# Top.net
KiCad netlist of a schematic drawn in Altium Designer
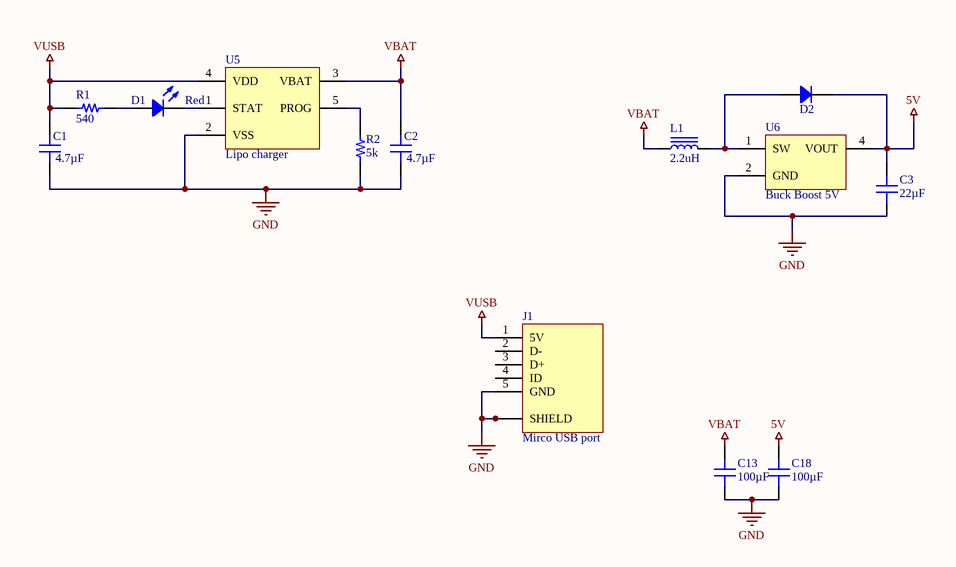
[diagram p0: Top.SchDoc]

(export (version "E")
  (design (tool "Eeschema 10.0.6"))
  (components
    (comp (ref "C1")
      (value "4.7µF")
      (footprint "CAP 0603_1608")
      (description "CAP CER 0.1UF 100V 0603 EPOXY")
      (fields
        (field (name "PART NUMBER") "GCG188R92A104KA03D")
        (field (name "MANUFACTURER") "Murata Electronics")
      )
      (libsource (lib "Celestial Altium Library - altium_library") (part "Capacitor"))
    )
    (comp (ref "C2")
      (value "4.7µF")
      (footprint "CAP 0603_1608")
      (description "CAP CER 0.1UF 100V 0603 EPOXY")
      (fields
        (field (name "PART NUMBER") "GCG188R92A104KA03D")
        (field (name "MANUFACTURER") "Murata Electronics")
      )
      (libsource (lib "Celestial Altium Library - altium_library") (part "Capacitor"))
    )
    (comp (ref "C3")
      (value "22µF")
      (footprint "CAP 1210_3225 - 2.8MM")
      (description "CAP CER 100UF 16V X5R 1210")
      (fields (field (name "PART NUMBER") "EMK325ABJ107MM-P") (field (name "MANUFACTURER") "Taiyo Yuden"))
      (libsource (lib "Celestial Altium Library - altium_library") (part "Capacitor"))
    )
    (comp (ref "C13")
      (value "100µF")
      (footprint "CAP 1210_3225 - 2.8MM")
      (description "CAP CER 100UF 16V X5R 1210")
      (fields (field (name "PART NUMBER") "EMK325ABJ107MM-P") (field (name "MANUFACTURER") "Taiyo Yuden"))
      (libsource (lib "Celestial Altium Library - altium_library") (part "Capacitor"))
    )
    (comp (ref "C18")
      (value "100µF")
      (footprint "CAP 1210_3225 - 2.8MM")
      (description "CAP CER 100UF 16V X5R 1210")
      (fields (field (name "PART NUMBER") "EMK325ABJ107MM-P") (field (name "MANUFACTURER") "Taiyo Yuden"))
      (libsource (lib "Celestial Altium Library - altium_library") (part "Capacitor"))
    )
    (comp (ref "D1")
      (value "Red")
      (footprint "LED 0603_1608 RED")
      (description "LED RED 0603 SMD")
      (fields (field (name "PART NUMBER") "5973005507F") (field (name "MANUFACTURER") "Dialight"))
      (libsource (lib "Celestial Altium Library - altium_library") (part "LED"))
    )
    (comp (ref "D2")
      (value "V1F6-M3/H")
      (footprint "SMF DO-219AB")
      (description "1A 60V SMF TRENCH SKY RECT")
      (fields (field (name "MANUFACTURER") "Vishay Semiconductor Diodes Division"))
      (libsource (lib "Celestial Altium Library - altium_library") (part "Diode"))
    )
    (comp (ref "J1")
      (value "Mirco USB port")
      (footprint "GCT_USB3131-30-0230-A_REVB")
      (description "USB - micro B USB 2.0 Receptacle Connector 5 Position Through Hole")
      (fields (field (name "MF") "Amphenol ICC") (field (name "MP") "10118194-0001LF"))
      (libsource (lib "IC") (part "USB3131-30-0230-A"))
    )
    (comp (ref "L1")
      (value "2.2uH")
      (footprint "TAIYO YUDEN MAMK2520T1R0M")
      (description "FIXED IND 470NH 3.2A 46 MOHM SMD")
      (fields (field (name "PART NUMBER") "MAKK2520TR47M") (field (name "MANUFACTURER") "Taiyo Yuden"))
      (libsource (lib "Celestial Altium Library - altium_library") (part "Inductor"))
    )
    (comp (ref "R1")
      (value "540")
      (footprint "RES 0603_1608")
      (description "RES 10K OHM 0.1% 1/16W 0603")
      (fields
        (field (name "PART NUMBER") "RNCS0603BKE10K0")
        (field (name "MANUFACTURER") "Stackpole Electronics Inc")
      )
      (libsource (lib "Celestial Altium Library - altium_library") (part "Resistor"))
    )
    (comp (ref "R2")
      (value "5k")
      (footprint "RES 0603_1608")
      (description "RES 10K OHM 0.1% 1/16W 0603")
      (fields
        (field (name "PART NUMBER") "RNCS0603BKE10K0")
        (field (name "MANUFACTURER") "Stackpole Electronics Inc")
      )
      (libsource (lib "Celestial Altium Library - altium_library") (part "Resistor"))
    )
    (comp (ref "U5")
      (value "Lipo charger")
      (footprint "TI SOT-23-5 DBV")
      (libsource (lib "IC") (part "MCP73831"))
    )
    (comp (ref "U6")
      (value "Buck Boost 5V")
      (footprint "TI SOT-23-5 DBV")
      (description "ADJ step down Buck")
      (libsource (lib "IC") (part "TPS613222A"))
    )
  )
  (nets
    (net (code "1") (name "5V") (class "Default")
      (node (ref "C18") (pin "2") (pinfunction "2_2") (pintype "passive"))
      (node (ref "C3") (pin "2") (pinfunction "2_2") (pintype "passive"))
      (node (ref "D2") (pin "2") (pinfunction "2_2") (pintype "passive"))
      (node (ref "U6") (pin "4") (pinfunction "VOUT_4") (pintype "passive"))
    )
    (net (code "2") (name "GND") (class "Default")
      (node (ref "C1") (pin "2") (pinfunction "2_2") (pintype "passive"))
      (node (ref "C13") (pin "1") (pinfunction "1_1") (pintype "passive"))
      (node (ref "C18") (pin "1") (pinfunction "1_1") (pintype "passive"))
      (node (ref "C2") (pin "2") (pinfunction "2_2") (pintype "passive"))
      (node (ref "C3") (pin "1") (pinfunction "1_1") (pintype "passive"))
      (node (ref "J1") (pin "5") (pinfunction "GND_5") (pintype "passive"))
      (node (ref "J1") (pin "S1") (pinfunction "SHIELD_S1") (pintype "passive"))
      (node (ref "J1") (pin "S2") (pinfunction "SHIELD_S2") (pintype "passive"))
      (node (ref "R2") (pin "2") (pinfunction "2_2") (pintype "passive"))
      (node (ref "U5") (pin "2") (pinfunction "VSS_2") (pintype "passive"))
      (node (ref "U6") (pin "2") (pinfunction "GND_2") (pintype "passive"))
    )
    (net (code "3") (name "Net-(D1-Pad1)") (class "Default")
      (node (ref "D1") (pin "1") (pinfunction "1_1") (pintype "passive"))
      (node (ref "R1") (pin "2") (pinfunction "2_2") (pintype "passive"))
    )
    (net (code "4") (name "Net-(U5-PROG)") (class "Default")
      (node (ref "R2") (pin "1") (pinfunction "1_1") (pintype "passive"))
      (node (ref "U5") (pin "5") (pinfunction "PROG_5") (pintype "passive"))
    )
    (net (code "5") (name "Net-(U5-STAT)") (class "Default")
      (node (ref "D1") (pin "2") (pinfunction "2_2") (pintype "passive"))
      (node (ref "U5") (pin "1") (pinfunction "STAT_1") (pintype "passive"))
    )
    (net (code "6") (name "Net-(U6-SW)") (class "Default")
      (node (ref "D2") (pin "1") (pinfunction "1_1") (pintype "passive"))
      (node (ref "L1") (pin "2") (pinfunction "2_2") (pintype "passive"))
      (node (ref "U6") (pin "1") (pinfunction "SW_1") (pintype "passive"))
    )
    (net (code "7") (name "VBAT") (class "Default")
      (node (ref "C13") (pin "2") (pinfunction "2_2") (pintype "passive"))
      (node (ref "C2") (pin "1") (pinfunction "1_1") (pintype "passive"))
      (node (ref "L1") (pin "1") (pinfunction "1_1") (pintype "passive"))
      (node (ref "U5") (pin "3") (pinfunction "VBAT_3") (pintype "passive"))
    )
    (net (code "8") (name "VUSB") (class "Default")
      (node (ref "C1") (pin "1") (pinfunction "1_1") (pintype "passive"))
      (node (ref "J1") (pin "1") (pinfunction "5V_1") (pintype "passive"))
      (node (ref "R1") (pin "1") (pinfunction "1_1") (pintype "passive"))
      (node (ref "U5") (pin "4") (pinfunction "VDD_4") (pintype "passive"))
    )
    (net (code "9") (name "unconnected-(J1-D+-Pad3)") (class "Default")
      (node (ref "J1") (pin "3") (pinfunction "D+_3") (pintype "passive"))
    )
    (net (code "10") (name "unconnected-(J1-D--Pad2)") (class "Default")
      (node (ref "J1") (pin "2") (pinfunction "D-_2") (pintype "passive"))
    )
    (net (code "11") (name "unconnected-(J1-ID-Pad4)") (class "Default")
      (node (ref "J1") (pin "4") (pinfunction "ID_4") (pintype "passive"))
    )
  )
)
